# SunriseClockMainv2.net
KiCad netlist of a schematic drawn in EAGLE
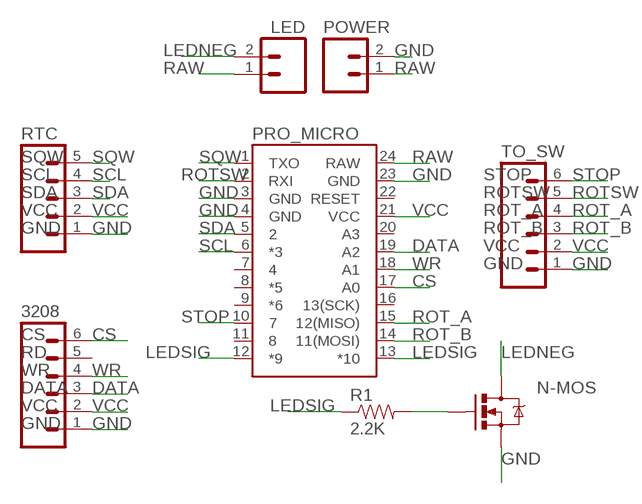
[diagram p0: schematic, sheet 1]

(export (version "E")
  (design (tool "Eeschema 10.0.6"))
  (components
    (comp (ref "3208")
      (value "M06LOCK")
      (footprint "eagle-import:1X06_LOCK")
      (libsource (lib "eagle-import") (part "M06LOCK"))
    )
    (comp (ref "LED")
      (value "M02LOCK")
      (footprint "eagle-import:1X02_LOCK")
      (libsource (lib "eagle-import") (part "M02LOCK"))
    )
    (comp (ref "N-MOS")
      (value "MOSFET-NCHANNELFQP30N06L")
      (footprint "eagle-import:TO220V")
      (libsource (lib "eagle-import") (part "MOSFET-NCHANNELFQP30N06L"))
    )
    (comp (ref "POWER")
      (value "M025MM")
      (footprint "eagle-import:SCREWTERMINAL-5MM-2")
      (libsource (lib "eagle-import") (part "M025MM"))
    )
    (comp (ref "PRO_MICRO")
      (value "ARDUINO_PRO_MICRO")
      (footprint "eagle-import:ARDUINO_PRO_MICRO")
      (libsource (lib "eagle-import") (part "ARDUINO_PRO_MICRO"))
    )
    (comp (ref "R1")
      (value "2.2K")
      (footprint "eagle-import:AXIAL-0.4")
      (libsource (lib "eagle-import") (part "RESISTORPTH-1/4W"))
    )
    (comp (ref "RTC")
      (value "M05LOCK")
      (footprint "eagle-import:1X05_LOCK")
      (libsource (lib "eagle-import") (part "M05LOCK"))
    )
    (comp (ref "TO_SW")
      (value "M06LOCK")
      (footprint "eagle-import:1X06_LOCK")
      (libsource (lib "eagle-import") (part "M06LOCK"))
    )
  )
  (nets
    (net (code "1") (name "/CS") (class "Default")
      (node (ref "3208") (pin "6") (pinfunction "6_6") (pintype "passive"))
      (node (ref "PRO_MICRO") (pin "17") (pinfunction "A0_17") (pintype "bidirectional"))
    )
    (net (code "2") (name "/DATA") (class "Default")
      (node (ref "3208") (pin "3") (pinfunction "3_3") (pintype "passive"))
      (node (ref "PRO_MICRO") (pin "19") (pinfunction "A2_19") (pintype "bidirectional"))
    )
    (net (code "3") (name "/GND") (class "Default")
      (node (ref "3208") (pin "1") (pinfunction "1_1") (pintype "passive"))
      (node (ref "N-MOS") (pin "3") (pinfunction "S_3") (pintype "passive"))
      (node (ref "POWER") (pin "2") (pinfunction "2_2") (pintype "passive"))
      (node (ref "PRO_MICRO") (pin "23") (pinfunction "GND_23") (pintype "bidirectional"))
      (node (ref "PRO_MICRO") (pin "3") (pinfunction "GND_3") (pintype "bidirectional"))
      (node (ref "PRO_MICRO") (pin "4") (pinfunction "GND_4") (pintype "bidirectional"))
      (node (ref "RTC") (pin "1") (pinfunction "1_1") (pintype "passive"))
      (node (ref "TO_SW") (pin "1") (pinfunction "1_1") (pintype "passive"))
    )
    (net (code "4") (name "/LEDNEG") (class "Default")
      (node (ref "LED") (pin "2") (pinfunction "2_2") (pintype "passive"))
      (node (ref "N-MOS") (pin "2") (pinfunction "D_2") (pintype "passive"))
    )
    (net (code "5") (name "/LEDSIG") (class "Default")
      (node (ref "PRO_MICRO") (pin "12") (pinfunction "*9_12") (pintype "bidirectional"))
      (node (ref "PRO_MICRO") (pin "13") (pinfunction "*10_13") (pintype "bidirectional"))
      (node (ref "R1") (pin "P$1") (pinfunction "1_P$1") (pintype "passive"))
    )
    (net (code "6") (name "/RAW") (class "Default")
      (node (ref "LED") (pin "1") (pinfunction "1_1") (pintype "passive"))
      (node (ref "POWER") (pin "1") (pinfunction "1_1") (pintype "passive"))
      (node (ref "PRO_MICRO") (pin "24") (pinfunction "RAW_24") (pintype "bidirectional"))
    )
    (net (code "7") (name "/ROTSW") (class "Default")
      (node (ref "PRO_MICRO") (pin "2") (pinfunction "RXI_2") (pintype "bidirectional"))
      (node (ref "TO_SW") (pin "5") (pinfunction "5_5") (pintype "passive"))
    )
    (net (code "8") (name "/ROT_A") (class "Default")
      (node (ref "PRO_MICRO") (pin "15") (pinfunction "12(MISO)_15") (pintype "bidirectional"))
      (node (ref "TO_SW") (pin "4") (pinfunction "4_4") (pintype "passive"))
    )
    (net (code "9") (name "/ROT_B") (class "Default")
      (node (ref "PRO_MICRO") (pin "14") (pinfunction "11(MOSI)_14") (pintype "bidirectional"))
      (node (ref "TO_SW") (pin "3") (pinfunction "3_3") (pintype "passive"))
    )
    (net (code "10") (name "/SCL") (class "Default")
      (node (ref "PRO_MICRO") (pin "6") (pinfunction "*3_6") (pintype "bidirectional"))
      (node (ref "RTC") (pin "4") (pinfunction "4_4") (pintype "passive"))
    )
    (net (code "11") (name "/SDA") (class "Default")
      (node (ref "PRO_MICRO") (pin "5") (pinfunction "2_5") (pintype "bidirectional"))
      (node (ref "RTC") (pin "3") (pinfunction "3_3") (pintype "passive"))
    )
    (net (code "12") (name "/SQW") (class "Default")
      (node (ref "PRO_MICRO") (pin "1") (pinfunction "TXO_1") (pintype "bidirectional"))
      (node (ref "RTC") (pin "5") (pinfunction "5_5") (pintype "passive"))
    )
    (net (code "13") (name "/STOP") (class "Default")
      (node (ref "PRO_MICRO") (pin "10") (pinfunction "7_10") (pintype "bidirectional"))
      (node (ref "TO_SW") (pin "6") (pinfunction "6_6") (pintype "passive"))
    )
    (net (code "14") (name "/VCC") (class "Default")
      (node (ref "3208") (pin "2") (pinfunction "2_2") (pintype "passive"))
      (node (ref "PRO_MICRO") (pin "21") (pinfunction "VCC_21") (pintype "bidirectional"))
      (node (ref "RTC") (pin "2") (pinfunction "2_2") (pintype "passive"))
      (node (ref "TO_SW") (pin "2") (pinfunction "2_2") (pintype "passive"))
    )
    (net (code "15") (name "/WR") (class "Default")
      (node (ref "3208") (pin "4") (pinfunction "4_4") (pintype "passive"))
      (node (ref "PRO_MICRO") (pin "18") (pinfunction "A1_18") (pintype "bidirectional"))
    )
    (net (code "16") (name "Net-(N-MOS-G)") (class "Default")
      (node (ref "N-MOS") (pin "1") (pinfunction "G_1") (pintype "passive"))
      (node (ref "R1") (pin "P$2") (pinfunction "2_P$2") (pintype "passive"))
    )
    (net (code "17") (name "unconnected-(3208-Pad5)") (class "Default")
      (node (ref "3208") (pin "5") (pinfunction "5_5") (pintype "passive"))
    )
    (net (code "18") (name "unconnected-(PRO_MICRO-*5-Pad8)") (class "Default")
      (node (ref "PRO_MICRO") (pin "8") (pinfunction "*5_8") (pintype "bidirectional"))
    )
    (net (code "19") (name "unconnected-(PRO_MICRO-*6-Pad9)") (class "Default")
      (node (ref "PRO_MICRO") (pin "9") (pinfunction "*6_9") (pintype "bidirectional"))
    )
    (net (code "20") (name "unconnected-(PRO_MICRO-4-Pad7)") (class "Default")
      (node (ref "PRO_MICRO") (pin "7") (pinfunction "4_7") (pintype "bidirectional"))
    )
    (net (code "21") (name "unconnected-(PRO_MICRO-8-Pad11)") (class "Default")
      (node (ref "PRO_MICRO") (pin "11") (pinfunction "8_11") (pintype "bidirectional"))
    )
    (net (code "22") (name "unconnected-(PRO_MICRO-13(SCK)-Pad16)") (class "Default")
      (node (ref "PRO_MICRO") (pin "16") (pinfunction "13(SCK)_16") (pintype "bidirectional"))
    )
    (net (code "23") (name "unconnected-(PRO_MICRO-A3-Pad20)") (class "Default")
      (node (ref "PRO_MICRO") (pin "20") (pinfunction "A3_20") (pintype "bidirectional"))
    )
    (net (code "24") (name "unconnected-(PRO_MICRO-RESET-Pad22)") (class "Default")
      (node (ref "PRO_MICRO") (pin "22") (pinfunction "RESET_22") (pintype "bidirectional"))
    )
  )
)
